# motordriver.net
KiCad netlist of a schematic drawn in EAGLE
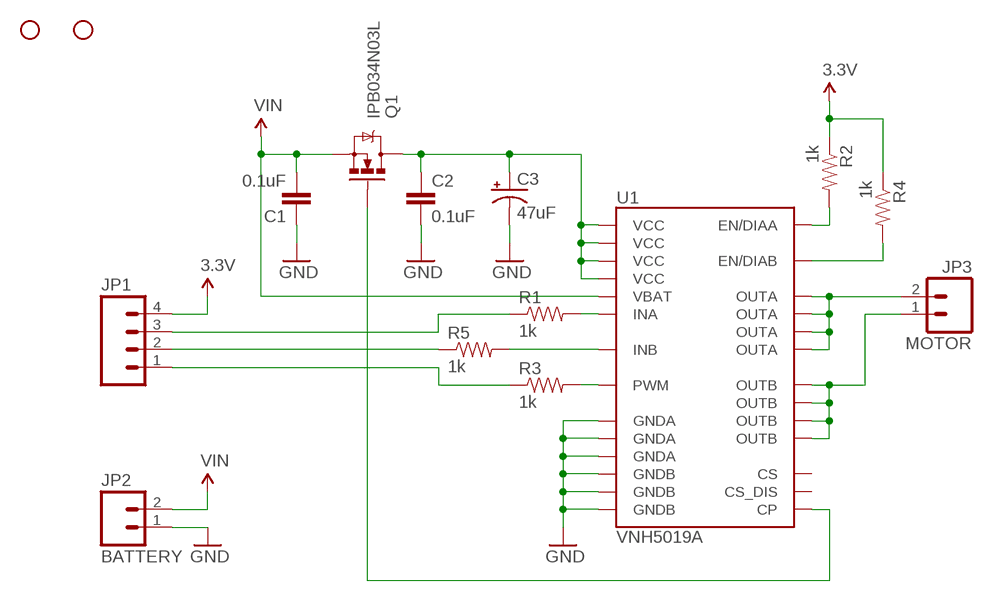
[diagram p0: schematic, sheet 1]

(export (version "E")
  (design (tool "Eeschema 10.0.6"))
  (components
    (comp (ref "C1")
      (value "0.1uF")
      (footprint "eagle-import:0805")
      (libsource (lib "eagle-import") (part "CAP0805"))
    )
    (comp (ref "C2")
      (value "0.1uF")
      (footprint "eagle-import:0805")
      (libsource (lib "eagle-import") (part "CAP0805"))
    )
    (comp (ref "C3")
      (value "47uF")
      (footprint "eagle-import:CPOL-RADIAL-100UF-25V")
      (libsource (lib "eagle-import") (part "CAP_POLPTH1"))
    )
    (comp (ref "JP1")
      (value "M04POLAR_LOCK")
      (footprint "eagle-import:MOLEX-1X4_LOCK")
      (libsource (lib "eagle-import") (part "M04POLAR_LOCK"))
    )
    (comp (ref "JP2")
      (value "BATTERY")
      (footprint "eagle-import:SCREWTERMINAL-5MM-2")
      (libsource (lib "eagle-import") (part "M025MM"))
    )
    (comp (ref "JP3")
      (value "MOTOR")
      (footprint "eagle-import:SCREWTERMINAL-5MM-2")
      (libsource (lib "eagle-import") (part "M025MM"))
    )
    (comp (ref "Q1")
      (value "IPB034N03L")
      (footprint "eagle-import:DPAK")
      (libsource (lib "eagle-import") (part "MOSFET-NCHANNELFDD8780"))
    )
    (comp (ref "R1")
      (value "1k")
      (footprint "eagle-import:0805")
      (libsource (lib "eagle-import") (part "RESISTOR0805-RES"))
    )
    (comp (ref "R2")
      (value "1k")
      (footprint "eagle-import:0805")
      (libsource (lib "eagle-import") (part "RESISTOR0805-RES"))
    )
    (comp (ref "R3")
      (value "1k")
      (footprint "eagle-import:0805")
      (libsource (lib "eagle-import") (part "RESISTOR0805-RES"))
    )
    (comp (ref "R4")
      (value "1k")
      (footprint "eagle-import:0805")
      (libsource (lib "eagle-import") (part "RESISTOR0805-RES"))
    )
    (comp (ref "R5")
      (value "1k")
      (footprint "eagle-import:0805")
      (libsource (lib "eagle-import") (part "RESISTOR0805-RES"))
    )
    (comp (ref "STANDOFF1")
      (value "STAND-OFF")
      (footprint "eagle-import:STAND-OFF")
      (libsource (lib "eagle-import") (part "STAND-OFF"))
    )
    (comp (ref "STANDOFF2")
      (value "STAND-OFF")
      (footprint "eagle-import:STAND-OFF")
      (libsource (lib "eagle-import") (part "STAND-OFF"))
    )
    (comp (ref "U1")
      (value "VNH5019A")
      (footprint "eagle-import:MULTIPOWERSO-30")
      (libsource (lib "eagle-import") (part "VNH5019A"))
    )
  )
  (nets
    (net (code "1") (name "3.3V") (class "Default")
      (node (ref "JP1") (pin "4") (pinfunction "4_4") (pintype "passive"))
      (node (ref "R2") (pin "1") (pinfunction "1_1") (pintype "passive"))
      (node (ref "R4") (pin "1") (pinfunction "1_1") (pintype "passive"))
    )
    (net (code "2") (name "GND") (class "Default")
      (node (ref "C1") (pin "1") (pinfunction "1_1") (pintype "passive"))
      (node (ref "C2") (pin "2") (pinfunction "2_2") (pintype "passive"))
      (node (ref "C3") (pin "2") (pinfunction "-_2") (pintype "passive"))
      (node (ref "JP2") (pin "1") (pinfunction "1_1") (pintype "passive"))
      (node (ref "U1") (pin "18") (pinfunction "GNDB_18") (pintype "bidirectional"))
      (node (ref "U1") (pin "19") (pinfunction "GNDB_19") (pintype "bidirectional"))
      (node (ref "U1") (pin "20") (pinfunction "GNDB_20") (pintype "bidirectional"))
      (node (ref "U1") (pin "26") (pinfunction "GNDA_26") (pintype "bidirectional"))
      (node (ref "U1") (pin "27") (pinfunction "GNDA_27") (pintype "bidirectional"))
      (node (ref "U1") (pin "28") (pinfunction "GNDA_28") (pintype "bidirectional"))
    )
    (net (code "3") (name "Net-(C3-+)") (class "Default")
      (node (ref "C2") (pin "1") (pinfunction "1_1") (pintype "passive"))
      (node (ref "C3") (pin "1") (pinfunction "+_1") (pintype "passive"))
      (node (ref "Q1") (pin "4") (pinfunction "D_4") (pintype "passive"))
      (node (ref "U1") (pin "13") (pinfunction "VCC_13") (pintype "bidirectional"))
      (node (ref "U1") (pin "23") (pinfunction "VCC_23") (pintype "bidirectional"))
      (node (ref "U1") (pin "3") (pinfunction "VCC_3") (pintype "bidirectional"))
      (node (ref "U1") (pin "SLUG1") (pinfunction "VCC_SLUG1") (pintype "bidirectional"))
    )
    (net (code "4") (name "Net-(JP1-Pad1)") (class "Default")
      (node (ref "JP1") (pin "1") (pinfunction "1_1") (pintype "passive"))
      (node (ref "R3") (pin "1") (pinfunction "1_1") (pintype "passive"))
    )
    (net (code "5") (name "Net-(JP1-Pad2)") (class "Default")
      (node (ref "JP1") (pin "2") (pinfunction "2_2") (pintype "passive"))
      (node (ref "R5") (pin "1") (pinfunction "1_1") (pintype "passive"))
    )
    (net (code "6") (name "Net-(JP1-Pad3)") (class "Default")
      (node (ref "JP1") (pin "3") (pinfunction "3_3") (pintype "passive"))
      (node (ref "R1") (pin "1") (pinfunction "1_1") (pintype "passive"))
    )
    (net (code "7") (name "Net-(JP3-Pad1)") (class "Default")
      (node (ref "JP3") (pin "1") (pinfunction "1_1") (pintype "passive"))
      (node (ref "U1") (pin "15") (pinfunction "OUTB_15") (pintype "bidirectional"))
      (node (ref "U1") (pin "16") (pinfunction "OUTB_16") (pintype "bidirectional"))
      (node (ref "U1") (pin "21") (pinfunction "OUTB_21") (pintype "bidirectional"))
      (node (ref "U1") (pin "SLUG2") (pinfunction "OUTB_SLUG2") (pintype "bidirectional"))
    )
    (net (code "8") (name "Net-(JP3-Pad2)") (class "Default")
      (node (ref "JP3") (pin "2") (pinfunction "2_2") (pintype "passive"))
      (node (ref "U1") (pin "1") (pinfunction "OUTA_1") (pintype "bidirectional"))
      (node (ref "U1") (pin "25") (pinfunction "OUTA_25") (pintype "bidirectional"))
      (node (ref "U1") (pin "30") (pinfunction "OUTA_30") (pintype "bidirectional"))
      (node (ref "U1") (pin "SLUG3") (pinfunction "OUTA_SLUG3") (pintype "bidirectional"))
    )
    (net (code "9") (name "Net-(Q1-G)") (class "Default")
      (node (ref "Q1") (pin "1") (pinfunction "G_1") (pintype "passive"))
      (node (ref "U1") (pin "11") (pinfunction "CP_11") (pintype "bidirectional"))
    )
    (net (code "10") (name "Net-(U1-EN{slash}DIAA)") (class "Default")
      (node (ref "R2") (pin "2") (pinfunction "2_2") (pintype "passive"))
      (node (ref "U1") (pin "5") (pinfunction "EN/DIAA_5") (pintype "bidirectional"))
    )
    (net (code "11") (name "Net-(U1-EN{slash}DIAB)") (class "Default")
      (node (ref "R4") (pin "2") (pinfunction "2_2") (pintype "passive"))
      (node (ref "U1") (pin "9") (pinfunction "EN/DIAB_9") (pintype "bidirectional"))
    )
    (net (code "12") (name "Net-(U1-INA)") (class "Default")
      (node (ref "R1") (pin "2") (pinfunction "2_2") (pintype "passive"))
      (node (ref "U1") (pin "4") (pinfunction "INA_4") (pintype "bidirectional"))
    )
    (net (code "13") (name "Net-(U1-INB)") (class "Default")
      (node (ref "R5") (pin "2") (pinfunction "2_2") (pintype "passive"))
      (node (ref "U1") (pin "10") (pinfunction "INB_10") (pintype "bidirectional"))
    )
    (net (code "14") (name "Net-(U1-PWM)") (class "Default")
      (node (ref "R3") (pin "2") (pinfunction "2_2") (pintype "passive"))
      (node (ref "U1") (pin "7") (pinfunction "PWM_7") (pintype "bidirectional"))
    )
    (net (code "15") (name "VIN") (class "Default")
      (node (ref "C1") (pin "2") (pinfunction "2_2") (pintype "passive"))
      (node (ref "JP2") (pin "2") (pinfunction "2_2") (pintype "passive"))
      (node (ref "Q1") (pin "3") (pinfunction "S_3") (pintype "passive"))
      (node (ref "U1") (pin "12") (pinfunction "VBAT_12") (pintype "bidirectional"))
    )
    (net (code "16") (name "unconnected-(U1-CS-Pad8)") (class "Default")
      (node (ref "U1") (pin "8") (pinfunction "CS_8") (pintype "bidirectional"))
    )
    (net (code "17") (name "unconnected-(U1-CS_DIS-Pad6)") (class "Default")
      (node (ref "U1") (pin "6") (pinfunction "CS_DIS_6") (pintype "bidirectional"))
    )
  )
)
